# powersupply_autorouter.net
KiCad netlist of a schematic drawn in EAGLE
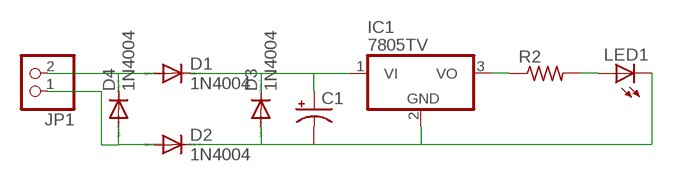
[diagram p0: schematic, sheet 1]

(export (version "E")
  (design (tool "Eeschema 10.0.6"))
  (components
    (comp (ref "C1")
      (value "CPOL-USE3.5-10")
      (footprint "eagle-import:E3,5-10")
      (libsource (lib "eagle-import") (part "CPOL-USE3.5-10"))
    )
    (comp (ref "D1")
      (value "1N4004")
      (footprint "eagle-import:DO41-10")
      (libsource (lib "eagle-import") (part "1N4004"))
    )
    (comp (ref "D2")
      (value "1N4004")
      (footprint "eagle-import:DO41-10")
      (libsource (lib "eagle-import") (part "1N4004"))
    )
    (comp (ref "D3")
      (value "1N4004")
      (footprint "eagle-import:DO41-10")
      (libsource (lib "eagle-import") (part "1N4004"))
    )
    (comp (ref "D4")
      (value "1N4004")
      (footprint "eagle-import:DO41-10")
      (libsource (lib "eagle-import") (part "1N4004"))
    )
    (comp (ref "IC1")
      (value "7805TV")
      (footprint "eagle-import:TO220V")
      (libsource (lib "eagle-import") (part "78TV05"))
    )
    (comp (ref "JP1")
      (value "PINHD-1X2")
      (footprint "eagle-import:1X02")
      (libsource (lib "eagle-import") (part "PINHD-1X2"))
    )
    (comp (ref "LED1")
      (value "LED3MM")
      (footprint "eagle-import:LED3MM")
      (libsource (lib "eagle-import") (part "LED3MM"))
    )
    (comp (ref "R2")
      (value "R-US_0207/10")
      (footprint "eagle-import:0207_10")
      (libsource (lib "eagle-import") (part "R-US_0207/10"))
    )
  )
  (nets
    (net (code "1") (name "Net-(D1-PadA)") (class "Default")
      (node (ref "D1") (pin "A") (pinfunction "A_A") (pintype "passive"))
      (node (ref "D4") (pin "C") (pinfunction "C_C") (pintype "passive"))
      (node (ref "JP1") (pin "2") (pinfunction "2_2") (pintype "passive"))
    )
    (net (code "2") (name "Net-(D2-PadA)") (class "Default")
      (node (ref "D2") (pin "A") (pinfunction "A_A") (pintype "passive"))
      (node (ref "D4") (pin "A") (pinfunction "A_A") (pintype "passive"))
      (node (ref "JP1") (pin "1") (pinfunction "1_1") (pintype "passive"))
    )
    (net (code "3") (name "Net-(IC1-GND)") (class "Default")
      (node (ref "C1") (pin "-") (pinfunction "-_-") (pintype "passive"))
      (node (ref "D2") (pin "C") (pinfunction "C_C") (pintype "passive"))
      (node (ref "D3") (pin "A") (pinfunction "A_A") (pintype "passive"))
      (node (ref "IC1") (pin "2") (pinfunction "GND_2") (pintype "passive"))
      (node (ref "LED1") (pin "K") (pinfunction "C_K") (pintype "passive"))
    )
    (net (code "4") (name "Net-(IC1-VI)") (class "Default")
      (node (ref "C1") (pin "+") (pinfunction "+_+") (pintype "passive"))
      (node (ref "D1") (pin "C") (pinfunction "C_C") (pintype "passive"))
      (node (ref "D3") (pin "C") (pinfunction "C_C") (pintype "passive"))
      (node (ref "IC1") (pin "1") (pinfunction "VI_1") (pintype "input"))
    )
    (net (code "5") (name "Net-(IC1-VO)") (class "Default")
      (node (ref "IC1") (pin "3") (pinfunction "VO_3") (pintype "passive"))
      (node (ref "R2") (pin "1") (pinfunction "1_1") (pintype "passive"))
    )
    (net (code "6") (name "Net-(LED1-PadA)") (class "Default")
      (node (ref "LED1") (pin "A") (pinfunction "A_A") (pintype "passive"))
      (node (ref "R2") (pin "2") (pinfunction "2_2") (pintype "passive"))
    )
  )
)
